# VFD_CLOCK.net
KiCad netlist of a schematic drawn in Altium Designer
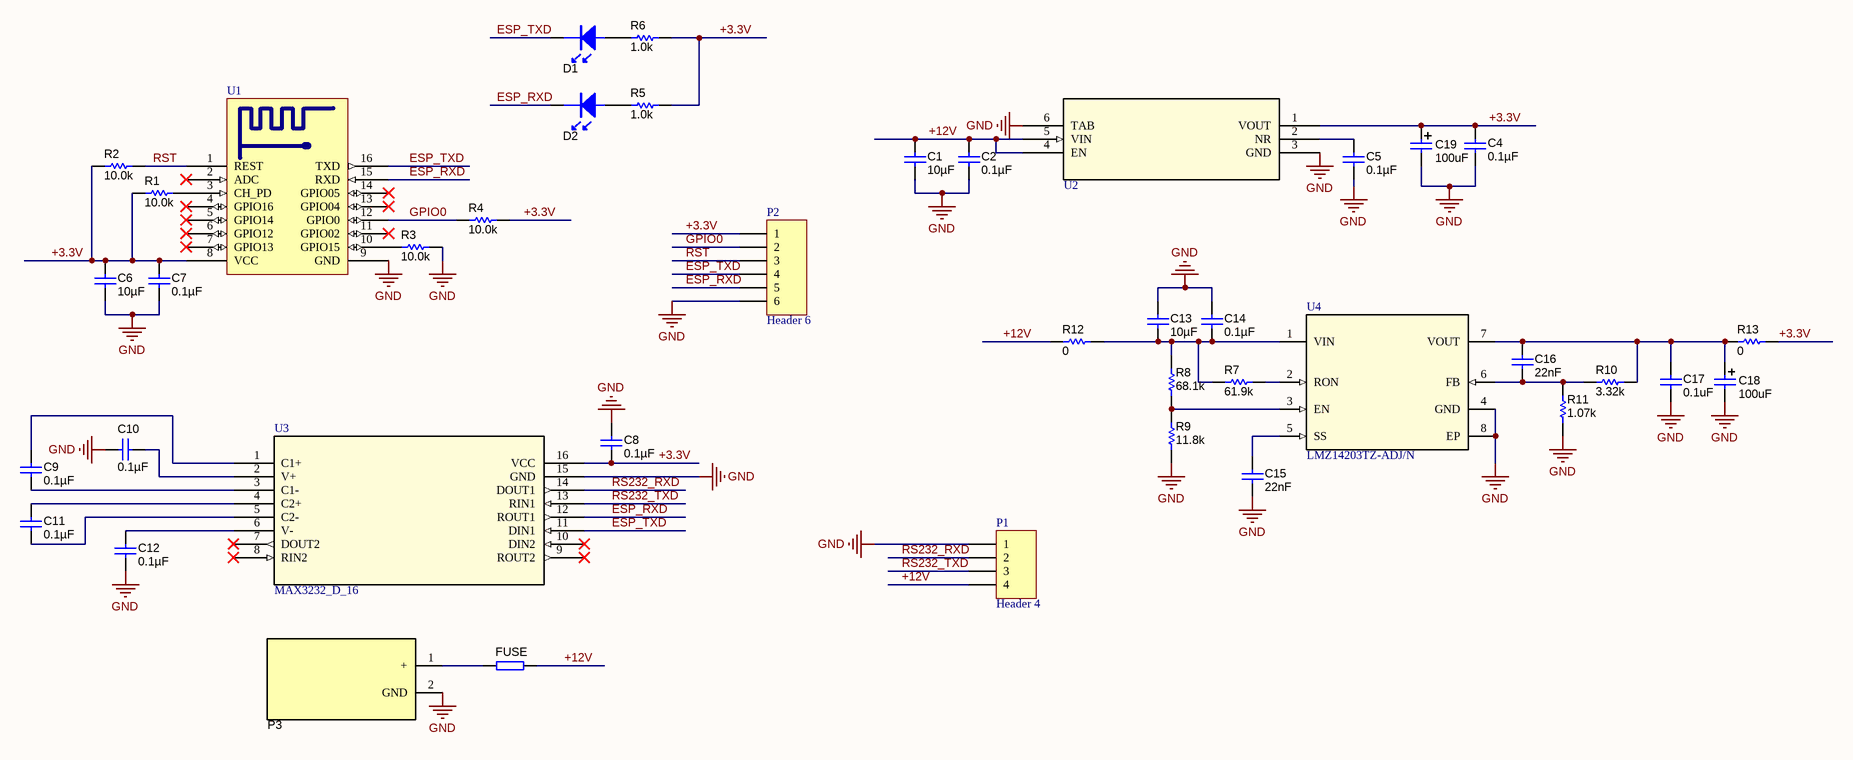
[diagram p0: VFD_CLOCK.SchDoc]

(export (version "E")
  (design (tool "Eeschema 10.0.6"))
  (components
    (comp (ref "C1")
      (value "0805YD106KAT2A")
      (footprint "0805_HV")
      (description "CAP, CERM, 10 µF, 16 V, +/- 10%, X5R, 0805")
      (fields
        (field (name "MANUFACTURER") "AVX")
        (field (name "VALUEDISPLAYED") "10µF")
        (field (name "PUBLISHER") "Texas Instruments")
      )
      (libsource (lib "VFD_CLOCK") (part "0805YD106KAT2A"))
    )
    (comp (ref "C2")
      (value "08051C103JAT2A")
      (footprint "0805_HV")
      (description "CAP, CERM, 0.01 µF, 100 V, +/- 5%, X7R, 0805")
      (fields
        (field (name "VALUEDISPLAYED") "0.1µF")
        (field (name "MANUFACTURER") "AVX")
        (field (name "PUBLISHER") "Texas Instruments")
      )
      (libsource (lib "VFD_CLOCK") (part "08051C103JAT2A"))
    )
    (comp (ref "C4")
      (value "08051C103JAT2A")
      (footprint "0805_HV")
      (description "CAP, CERM, 0.01 µF, 100 V, +/- 5%, X7R, 0805")
      (fields
        (field (name "VALUEDISPLAYED") "0.1µF")
        (field (name "MANUFACTURER") "AVX")
        (field (name "PUBLISHER") "Texas Instruments")
      )
      (libsource (lib "VFD_CLOCK") (part "08051C103JAT2A"))
    )
    (comp (ref "C5")
      (value "08051C103JAT2A")
      (footprint "0805_HV")
      (description "CAP, CERM, 0.01 µF, 100 V, +/- 5%, X7R, 0805")
      (fields
        (field (name "VALUEDISPLAYED") "0.1µF")
        (field (name "MANUFACTURER") "AVX")
        (field (name "PUBLISHER") "Texas Instruments")
      )
      (libsource (lib "VFD_CLOCK") (part "08051C103JAT2A"))
    )
    (comp (ref "C6")
      (value "0805YD106KAT2A")
      (footprint "0805_HV")
      (description "CAP, CERM, 10 µF, 16 V, +/- 10%, X5R, 0805")
      (fields
        (field (name "MANUFACTURER") "AVX")
        (field (name "VALUEDISPLAYED") "10µF")
        (field (name "PUBLISHER") "Texas Instruments")
      )
      (libsource (lib "VFD_CLOCK") (part "0805YD106KAT2A"))
    )
    (comp (ref "C7")
      (value "08051C103JAT2A")
      (footprint "0805_HV")
      (description "CAP, CERM, 0.01 µF, 100 V, +/- 5%, X7R, 0805")
      (fields
        (field (name "VALUEDISPLAYED") "0.1µF")
        (field (name "MANUFACTURER") "AVX")
        (field (name "PUBLISHER") "Texas Instruments")
      )
      (libsource (lib "VFD_CLOCK") (part "08051C103JAT2A"))
    )
    (comp (ref "C8")
      (value "08051C103JAT2A")
      (footprint "0805_HV")
      (description "CAP, CERM, 0.01 µF, 100 V, +/- 5%, X7R, 0805")
      (fields
        (field (name "VALUEDISPLAYED") "0.1µF")
        (field (name "MANUFACTURER") "AVX")
        (field (name "PUBLISHER") "Texas Instruments")
      )
      (libsource (lib "VFD_CLOCK") (part "08051C103JAT2A"))
    )
    (comp (ref "C9")
      (value "08051C103JAT2A")
      (footprint "0805_HV")
      (description "CAP, CERM, 0.01 µF, 100 V, +/- 5%, X7R, 0805")
      (fields
        (field (name "VALUEDISPLAYED") "0.1µF")
        (field (name "MANUFACTURER") "AVX")
        (field (name "PUBLISHER") "Texas Instruments")
      )
      (libsource (lib "VFD_CLOCK") (part "08051C103JAT2A"))
    )
    (comp (ref "C10")
      (value "08051C103JAT2A")
      (footprint "0805_HV")
      (description "CAP, CERM, 0.01 µF, 100 V, +/- 5%, X7R, 0805")
      (fields
        (field (name "VALUEDISPLAYED") "0.1µF")
        (field (name "MANUFACTURER") "AVX")
        (field (name "PUBLISHER") "Texas Instruments")
      )
      (libsource (lib "VFD_CLOCK") (part "08051C103JAT2A"))
    )
    (comp (ref "C11")
      (value "08051C103JAT2A")
      (footprint "0805_HV")
      (description "CAP, CERM, 0.01 µF, 100 V, +/- 5%, X7R, 0805")
      (fields
        (field (name "VALUEDISPLAYED") "0.1µF")
        (field (name "MANUFACTURER") "AVX")
        (field (name "PUBLISHER") "Texas Instruments")
      )
      (libsource (lib "VFD_CLOCK") (part "08051C103JAT2A"))
    )
    (comp (ref "C12")
      (value "08051C103JAT2A")
      (footprint "0805_HV")
      (description "CAP, CERM, 0.01 µF, 100 V, +/- 5%, X7R, 0805")
      (fields
        (field (name "VALUEDISPLAYED") "0.1µF")
        (field (name "MANUFACTURER") "AVX")
        (field (name "PUBLISHER") "Texas Instruments")
      )
      (libsource (lib "VFD_CLOCK") (part "08051C103JAT2A"))
    )
    (comp (ref "C13")
      (value "0805YD106KAT2A")
      (footprint "0805_HV")
      (description "CAP, CERM, 10 µF, 16 V, +/- 10%, X5R, 0805")
      (fields
        (field (name "MANUFACTURER") "AVX")
        (field (name "VALUEDISPLAYED") "10µF")
        (field (name "PUBLISHER") "Texas Instruments")
      )
      (libsource (lib "VFD_CLOCK") (part "0805YD106KAT2A"))
    )
    (comp (ref "C14")
      (value "08051C103JAT2A")
      (footprint "0805_HV")
      (description "CAP, CERM, 0.01 µF, 100 V, +/- 5%, X7R, 0805")
      (fields
        (field (name "VALUEDISPLAYED") "0.1µF")
        (field (name "MANUFACTURER") "AVX")
        (field (name "PUBLISHER") "Texas Instruments")
      )
      (libsource (lib "VFD_CLOCK") (part "08051C103JAT2A"))
    )
    (comp (ref "C15")
      (value "08051C103JAT2A")
      (footprint "0805_HV")
      (description "CAP, CERM, 0.01 µF, 100 V, +/- 5%, X7R, 0805")
      (fields
        (field (name "VALUEDISPLAYED") "22nF")
        (field (name "MANUFACTURER") "AVX")
        (field (name "PUBLISHER") "Texas Instruments")
      )
      (libsource (lib "VFD_CLOCK") (part "08051C103JAT2A"))
    )
    (comp (ref "C16")
      (value "08051C103JAT2A")
      (footprint "0805_HV")
      (description "CAP, CERM, 0.01 µF, 100 V, +/- 5%, X7R, 0805")
      (fields
        (field (name "VALUEDISPLAYED") "22nF")
        (field (name "MANUFACTURER") "AVX")
        (field (name "PUBLISHER") "Texas Instruments")
      )
      (libsource (lib "VFD_CLOCK") (part "08051C103JAT2A"))
    )
    (comp (ref "C17")
      (value "08051C103JAT2A")
      (footprint "0805_HV")
      (description "CAP, CERM, 0.01 µF, 100 V, +/- 5%, X7R, 0805")
      (fields
        (field (name "VALUEDISPLAYED") "0.1uF")
        (field (name "MANUFACTURER") "AVX")
        (field (name "PUBLISHER") "Texas Instruments")
      )
      (libsource (lib "VFD_CLOCK") (part "08051C103JAT2A"))
    )
    (comp (ref "C18")
      (value "100uF")
      (footprint "CAP")
      (fields (field (name "MANUFACTURER") "Used in BOM report"))
      (libsource (lib "Buffer_Board") (part "Cap_100uF"))
    )
    (comp (ref "C19")
      (value "100uF")
      (footprint "CAP")
      (fields (field (name "MANUFACTURER") "Used in BOM report"))
      (libsource (lib "Buffer_Board") (part "Cap_100uF"))
    )
    (comp (ref "D1")
      (value "RED")
      (footprint "LED0805")
      (description "LED发光管")
      (libsource (lib "Buffer_Board") (part "LED"))
    )
    (comp (ref "D2")
      (value "RED")
      (footprint "LED0805")
      (description "LED发光管")
      (libsource (lib "Buffer_Board") (part "LED"))
    )
    (comp (ref "FUSE")
      (value "~")
      (footprint "1206")
      (description "电阻")
      (libsource (lib "Buffer_Board") (part "R"))
    )
    (comp (ref "P1")
      (value "Header 4")
      (footprint "HDR1X4")
      (description "Header, 4-Pin")
      (fields (field (name "PUBLISHER") "Altium Limited"))
      (libsource (lib "Miscellaneous Connectors") (part "Header 4"))
    )
    (comp (ref "P2")
      (value "Header 6")
      (footprint "HDR1X6")
      (description "Header, 6-Pin")
      (fields (field (name "PUBLISHER") "Altium Limited"))
      (libsource (lib "VFD_CLOCK") (part "Header 6"))
    )
    (comp (ref "P3")
      (value "Used in BOM report")
      (footprint "PWR5.5")
      (libsource (lib "VFD_CLOCK") (part "PWR5.5"))
    )
    (comp (ref "R1")
      (value "CRCW080510K0FKEA")
      (footprint "0805_HV")
      (description "RES, 10.0 k, 1%, 0.125 W, 0805")
      (fields
        (field (name "MANUFACTURER") "Vishay-Dale")
        (field (name "VALUEDISPLAYED") "10.0k")
        (field (name "PUBLISHER") "Texas Instruments")
      )
      (libsource (lib "VFD_CLOCK") (part "CRCW080510K0FKEA"))
    )
    (comp (ref "R2")
      (value "CRCW080510K0FKEA")
      (footprint "0805_HV")
      (description "RES, 10.0 k, 1%, 0.125 W, 0805")
      (fields
        (field (name "MANUFACTURER") "Vishay-Dale")
        (field (name "VALUEDISPLAYED") "10.0k")
        (field (name "PUBLISHER") "Texas Instruments")
      )
      (libsource (lib "VFD_CLOCK") (part "CRCW080510K0FKEA"))
    )
    (comp (ref "R3")
      (value "CRCW080510K0FKEA")
      (footprint "0805_HV")
      (description "RES, 10.0 k, 1%, 0.125 W, 0805")
      (fields
        (field (name "MANUFACTURER") "Vishay-Dale")
        (field (name "VALUEDISPLAYED") "10.0k")
        (field (name "PUBLISHER") "Texas Instruments")
      )
      (libsource (lib "VFD_CLOCK") (part "CRCW080510K0FKEA"))
    )
    (comp (ref "R4")
      (value "CRCW080510K0FKEA")
      (footprint "0805_HV")
      (description "RES, 10.0 k, 1%, 0.125 W, 0805")
      (fields
        (field (name "MANUFACTURER") "Vishay-Dale")
        (field (name "VALUEDISPLAYED") "10.0k")
        (field (name "PUBLISHER") "Texas Instruments")
      )
      (libsource (lib "VFD_CLOCK") (part "CRCW080510K0FKEA"))
    )
    (comp (ref "R5")
      (value "CRCW080510K0FKEA")
      (footprint "0805_HV")
      (description "RES, 10.0 k, 1%, 0.125 W, 0805")
      (fields
        (field (name "MANUFACTURER") "Vishay-Dale")
        (field (name "VALUEDISPLAYED") "1.0k")
        (field (name "PUBLISHER") "Texas Instruments")
      )
      (libsource (lib "VFD_CLOCK") (part "CRCW080510K0FKEA"))
    )
    (comp (ref "R6")
      (value "CRCW080510K0FKEA")
      (footprint "0805_HV")
      (description "RES, 10.0 k, 1%, 0.125 W, 0805")
      (fields
        (field (name "MANUFACTURER") "Vishay-Dale")
        (field (name "VALUEDISPLAYED") "1.0k")
        (field (name "PUBLISHER") "Texas Instruments")
      )
      (libsource (lib "VFD_CLOCK") (part "CRCW080510K0FKEA"))
    )
    (comp (ref "R7")
      (value "CRCW080510K0FKEA")
      (footprint "0805_HV")
      (description "RES, 10.0 k, 1%, 0.125 W, 0805")
      (fields
        (field (name "MANUFACTURER") "Vishay-Dale")
        (field (name "VALUEDISPLAYED") "61.9k")
        (field (name "PUBLISHER") "Texas Instruments")
      )
      (libsource (lib "VFD_CLOCK") (part "CRCW080510K0FKEA"))
    )
    (comp (ref "R8")
      (value "CRCW080510K0FKEA")
      (footprint "0805_HV")
      (description "RES, 10.0 k, 1%, 0.125 W, 0805")
      (fields
        (field (name "MANUFACTURER") "Vishay-Dale")
        (field (name "VALUEDISPLAYED") "68.1k")
        (field (name "PUBLISHER") "Texas Instruments")
      )
      (libsource (lib "VFD_CLOCK") (part "CRCW080510K0FKEA"))
    )
    (comp (ref "R9")
      (value "CRCW080510K0FKEA")
      (footprint "0805_HV")
      (description "RES, 10.0 k, 1%, 0.125 W, 0805")
      (fields
        (field (name "MANUFACTURER") "Vishay-Dale")
        (field (name "VALUEDISPLAYED") "11.8k")
        (field (name "PUBLISHER") "Texas Instruments")
      )
      (libsource (lib "VFD_CLOCK") (part "CRCW080510K0FKEA"))
    )
    (comp (ref "R10")
      (value "CRCW080510K0FKEA")
      (footprint "0805_HV")
      (description "RES, 10.0 k, 1%, 0.125 W, 0805")
      (fields
        (field (name "MANUFACTURER") "Vishay-Dale")
        (field (name "VALUEDISPLAYED") "3.32k")
        (field (name "PUBLISHER") "Texas Instruments")
      )
      (libsource (lib "VFD_CLOCK") (part "CRCW080510K0FKEA"))
    )
    (comp (ref "R11")
      (value "CRCW080510K0FKEA")
      (footprint "0805_HV")
      (description "RES, 10.0 k, 1%, 0.125 W, 0805")
      (fields
        (field (name "MANUFACTURER") "Vishay-Dale")
        (field (name "VALUEDISPLAYED") "1.07k")
        (field (name "PUBLISHER") "Texas Instruments")
      )
      (libsource (lib "VFD_CLOCK") (part "CRCW080510K0FKEA"))
    )
    (comp (ref "R12")
      (value "CRCW080510K0FKEA")
      (footprint "0805_HV")
      (description "RES, 10.0 k, 1%, 0.125 W, 0805")
      (fields
        (field (name "MANUFACTURER") "Vishay-Dale")
        (field (name "VALUEDISPLAYED") "0")
        (field (name "PUBLISHER") "Texas Instruments")
      )
      (libsource (lib "VFD_CLOCK") (part "CRCW080510K0FKEA"))
    )
    (comp (ref "R13")
      (value "CRCW080510K0FKEA")
      (footprint "0805_HV")
      (description "RES, 10.0 k, 1%, 0.125 W, 0805")
      (fields
        (field (name "MANUFACTURER") "Vishay-Dale")
        (field (name "VALUEDISPLAYED") "0")
        (field (name "PUBLISHER") "Texas Instruments")
      )
      (libsource (lib "VFD_CLOCK") (part "CRCW080510K0FKEA"))
    )
    (comp (ref "U1") (value "ESP-12") (footprint "ESP_12") (libsource (lib "ESP-12") (part "ESP-12")))
    (comp (ref "U2")
      (value "REG104-33")
      (footprint "TO-263")
      (description "Imported")
      (fields (field (name "MANUFACTURER_PART_NUMBER") "lp38502ts-adjnopb"))
      (libsource (lib "2019-04-22_16-58-03") (part "REG104-33"))
    )
    (comp (ref "U3")
      (value "MAX3232_D_16")
      (footprint "D16")
      (description "Imported")
      (fields
        (field (name "MANUFACTURER") "Texas Instruments")
        (field (name "GENERIC_PART_NUMBER") "MAX3232")
      )
      (libsource (lib "2019-04-22_17-42-02") (part "MAX3232_D_16"))
    )
    (comp (ref "U4")
      (value "LMZ14203TZ-ADJ/N")
      (footprint "NDW0007A")
      (description "Imported")
      (fields
        (field (name "MANUFACTURER") "Texas Instruments")
        (field (name "PARTNUMBER") "LMZ14203TZ-ADJ/NOPB")
      )
      (libsource (lib "2019-04-23_14-14-10") (part "LMZ14203TZ-ADJ/N"))
    )
  )
  (nets
    (net (code "1") (name "/+3.3V") (class "Default")
      (node (ref "C19") (pin "1") (pinfunction "1_1") (pintype "passive"))
      (node (ref "C4") (pin "1") (pinfunction "1_1") (pintype "passive"))
      (node (ref "C6") (pin "1") (pinfunction "1_1") (pintype "passive"))
      (node (ref "C7") (pin "1") (pinfunction "1_1") (pintype "passive"))
      (node (ref "C8") (pin "1") (pinfunction "1_1") (pintype "passive"))
      (node (ref "P2") (pin "1") (pinfunction "1_1") (pintype "passive"))
      (node (ref "R1") (pin "2") (pinfunction "2_2") (pintype "passive"))
      (node (ref "R13") (pin "2") (pinfunction "2_2") (pintype "passive"))
      (node (ref "R2") (pin "2") (pinfunction "2_2") (pintype "passive"))
      (node (ref "R4") (pin "1") (pinfunction "1_1") (pintype "passive"))
      (node (ref "R5") (pin "1") (pinfunction "1_1") (pintype "passive"))
      (node (ref "R6") (pin "1") (pinfunction "1_1") (pintype "passive"))
      (node (ref "U1") (pin "8") (pinfunction "VCC_8") (pintype "power_in"))
      (node (ref "U2") (pin "1") (pinfunction "VOUT_1") (pintype "passive"))
      (node (ref "U3") (pin "16") (pinfunction "VCC_16") (pintype "power_in"))
    )
    (net (code "2") (name "/+12V") (class "Default")
      (node (ref "C1") (pin "1") (pinfunction "1_1") (pintype "passive"))
      (node (ref "C2") (pin "1") (pinfunction "1_1") (pintype "passive"))
      (node (ref "FUSE") (pin "2") (pinfunction "2_2") (pintype "passive"))
      (node (ref "P1") (pin "4") (pinfunction "4_4") (pintype "passive"))
      (node (ref "R12") (pin "1") (pinfunction "1_1") (pintype "passive"))
      (node (ref "U2") (pin "4") (pinfunction "EN_4") (pintype "power_in"))
      (node (ref "U2") (pin "5") (pinfunction "VIN_5") (pintype "input"))
    )
    (net (code "3") (name "/ESP_RXD") (class "Default")
      (node (ref "D2") (pin "2") (pinfunction "2_2") (pintype "passive"))
      (node (ref "P2") (pin "5") (pinfunction "5_5") (pintype "passive"))
      (node (ref "U1") (pin "15") (pinfunction "RXD_15") (pintype "input"))
      (node (ref "U3") (pin "12") (pinfunction "ROUT1_12") (pintype "output"))
    )
    (net (code "4") (name "/ESP_TXD") (class "Default")
      (node (ref "D1") (pin "2") (pinfunction "2_2") (pintype "passive"))
      (node (ref "P2") (pin "4") (pinfunction "4_4") (pintype "passive"))
      (node (ref "U1") (pin "16") (pinfunction "TXD_16") (pintype "output"))
      (node (ref "U3") (pin "11") (pinfunction "DIN1_11") (pintype "input"))
    )
    (net (code "5") (name "/GPIO0") (class "Default")
      (node (ref "P2") (pin "2") (pinfunction "2_2") (pintype "passive"))
      (node (ref "R4") (pin "2") (pinfunction "2_2") (pintype "passive"))
      (node (ref "U1") (pin "12") (pinfunction "GPIO0_12") (pintype "bidirectional"))
    )
    (net (code "6") (name "/RS232_RXD") (class "Default")
      (node (ref "P1") (pin "2") (pinfunction "2_2") (pintype "passive"))
      (node (ref "U3") (pin "14") (pinfunction "DOUT1_14") (pintype "output"))
    )
    (net (code "7") (name "/RS232_TXD") (class "Default")
      (node (ref "P1") (pin "3") (pinfunction "3_3") (pintype "passive"))
      (node (ref "U3") (pin "13") (pinfunction "RIN1_13") (pintype "input"))
    )
    (net (code "8") (name "/RST") (class "Default")
      (node (ref "P2") (pin "3") (pinfunction "3_3") (pintype "passive"))
      (node (ref "R2") (pin "1") (pinfunction "1_1") (pintype "passive"))
      (node (ref "U1") (pin "1") (pinfunction "REST_1") (pintype "passive"))
    )
    (net (code "9") (name "GND") (class "Default")
      (node (ref "C1") (pin "2") (pinfunction "2_2") (pintype "passive"))
      (node (ref "C10") (pin "2") (pinfunction "2_2") (pintype "passive"))
      (node (ref "C12") (pin "2") (pinfunction "2_2") (pintype "passive"))
      (node (ref "C13") (pin "1") (pinfunction "1_1") (pintype "passive"))
      (node (ref "C14") (pin "1") (pinfunction "1_1") (pintype "passive"))
      (node (ref "C15") (pin "1") (pinfunction "1_1") (pintype "passive"))
      (node (ref "C17") (pin "1") (pinfunction "1_1") (pintype "passive"))
      (node (ref "C18") (pin "2") (pinfunction "2_2") (pintype "passive"))
      (node (ref "C19") (pin "2") (pinfunction "2_2") (pintype "passive"))
      (node (ref "C2") (pin "2") (pinfunction "2_2") (pintype "passive"))
      (node (ref "C4") (pin "2") (pinfunction "2_2") (pintype "passive"))
      (node (ref "C5") (pin "2") (pinfunction "2_2") (pintype "passive"))
      (node (ref "C6") (pin "2") (pinfunction "2_2") (pintype "passive"))
      (node (ref "C7") (pin "2") (pinfunction "2_2") (pintype "passive"))
      (node (ref "C8") (pin "2") (pinfunction "2_2") (pintype "passive"))
      (node (ref "P1") (pin "1") (pinfunction "1_1") (pintype "passive"))
      (node (ref "P2") (pin "6") (pinfunction "6_6") (pintype "passive"))
      (node (ref "P3") (pin "2") (pinfunction "GND_2") (pintype "passive"))
      (node (ref "R11") (pin "2") (pinfunction "2_2") (pintype "passive"))
      (node (ref "R3") (pin "1") (pinfunction "1_1") (pintype "passive"))
      (node (ref "R9") (pin "2") (pinfunction "2_2") (pintype "passive"))
      (node (ref "U1") (pin "9") (pinfunction "GND_9") (pintype "power_in"))
      (node (ref "U2") (pin "3") (pinfunction "GND_3") (pintype "power_in"))
      (node (ref "U2") (pin "6") (pinfunction "TAB_6") (pintype "power_in"))
      (node (ref "U3") (pin "15") (pinfunction "GND_15") (pintype "power_in"))
      (node (ref "U4") (pin "4") (pinfunction "GND_4") (pintype "power_in"))
      (node (ref "U4") (pin "8") (pinfunction "EP_8") (pintype "power_in"))
    )
    (net (code "10") (name "Net-(D1-Pad1)") (class "Default")
      (node (ref "D1") (pin "1") (pinfunction "1_1") (pintype "passive"))
      (node (ref "R6") (pin "2") (pinfunction "2_2") (pintype "passive"))
    )
    (net (code "11") (name "Net-(D2-Pad1)") (class "Default")
      (node (ref "D2") (pin "1") (pinfunction "1_1") (pintype "passive"))
      (node (ref "R5") (pin "2") (pinfunction "2_2") (pintype "passive"))
    )
    (net (code "12") (name "Net-(P3-+)") (class "Default")
      (node (ref "FUSE") (pin "1") (pinfunction "1_1") (pintype "passive"))
      (node (ref "P3") (pin "1") (pinfunction "+_1") (pintype "passive"))
    )
    (net (code "13") (name "Net-(U1-CH_PD)") (class "Default")
      (node (ref "R1") (pin "1") (pinfunction "1_1") (pintype "passive"))
      (node (ref "U1") (pin "3") (pinfunction "CH_PD_3") (pintype "input"))
    )
    (net (code "14") (name "Net-(U1-GPIO15)") (class "Default")
      (node (ref "R3") (pin "2") (pinfunction "2_2") (pintype "passive"))
      (node (ref "U1") (pin "10") (pinfunction "GPIO15_10") (pintype "bidirectional"))
    )
    (net (code "15") (name "Net-(U2-NR)") (class "Default")
      (node (ref "C5") (pin "1") (pinfunction "1_1") (pintype "passive"))
      (node (ref "U2") (pin "2") (pinfunction "NR_2") (pintype "power_in"))
    )
    (net (code "16") (name "Net-(U3-C1+)") (class "Default")
      (node (ref "C9") (pin "2") (pinfunction "2_2") (pintype "passive"))
      (node (ref "U3") (pin "1") (pinfunction "C1+_1") (pintype "passive"))
    )
    (net (code "17") (name "Net-(U3-C1-)") (class "Default")
      (node (ref "C9") (pin "1") (pinfunction "1_1") (pintype "passive"))
      (node (ref "U3") (pin "3") (pinfunction "C1-_3") (pintype "passive"))
    )
    (net (code "18") (name "Net-(U3-C2+)") (class "Default")
      (node (ref "C11") (pin "2") (pinfunction "2_2") (pintype "passive"))
      (node (ref "U3") (pin "4") (pinfunction "C2+_4") (pintype "passive"))
    )
    (net (code "19") (name "Net-(U3-C2-)") (class "Default")
      (node (ref "C11") (pin "1") (pinfunction "1_1") (pintype "passive"))
      (node (ref "U3") (pin "5") (pinfunction "C2-_5") (pintype "passive"))
    )
    (net (code "20") (name "Net-(U3-V+)") (class "Default")
      (node (ref "C10") (pin "1") (pinfunction "1_1") (pintype "passive"))
      (node (ref "U3") (pin "2") (pinfunction "V+_2") (pintype "power_in"))
    )
    (net (code "21") (name "Net-(U3-V-)") (class "Default")
      (node (ref "C12") (pin "1") (pinfunction "1_1") (pintype "passive"))
      (node (ref "U3") (pin "6") (pinfunction "V-_6") (pintype "power_in"))
    )
    (net (code "22") (name "Net-(U4-EN)") (class "Default")
      (node (ref "R8") (pin "2") (pinfunction "2_2") (pintype "passive"))
      (node (ref "R9") (pin "1") (pinfunction "1_1") (pintype "passive"))
      (node (ref "U4") (pin "3") (pinfunction "EN_3") (pintype "input"))
    )
    (net (code "23") (name "Net-(U4-FB)") (class "Default")
      (node (ref "C16") (pin "1") (pinfunction "1_1") (pintype "passive"))
      (node (ref "R10") (pin "1") (pinfunction "1_1") (pintype "passive"))
      (node (ref "R11") (pin "1") (pinfunction "1_1") (pintype "passive"))
      (node (ref "U4") (pin "6") (pinfunction "FB_6") (pintype "input"))
    )
    (net (code "24") (name "Net-(U4-RON)") (class "Default")
      (node (ref "R7") (pin "1") (pinfunction "1_1") (pintype "passive"))
      (node (ref "U4") (pin "2") (pinfunction "RON_2") (pintype "input"))
    )
    (net (code "25") (name "Net-(U4-SS)") (class "Default")
      (node (ref "C15") (pin "2") (pinfunction "2_2") (pintype "passive"))
      (node (ref "U4") (pin "5") (pinfunction "SS_5") (pintype "input"))
    )
    (net (code "26") (name "Net-(U4-VIN)") (class "Default")
      (node (ref "C13") (pin "2") (pinfunction "2_2") (pintype "passive"))
      (node (ref "C14") (pin "2") (pinfunction "2_2") (pintype "passive"))
      (node (ref "R12") (pin "2") (pinfunction "2_2") (pintype "passive"))
      (node (ref "R7") (pin "2") (pinfunction "2_2") (pintype "passive"))
      (node (ref "R8") (pin "1") (pinfunction "1_1") (pintype "passive"))
      (node (ref "U4") (pin "1") (pinfunction "VIN_1") (pintype "power_in"))
    )
    (net (code "27") (name "Net-(U4-VOUT)") (class "Default")
      (node (ref "C16") (pin "2") (pinfunction "2_2") (pintype "passive"))
      (node (ref "C17") (pin "2") (pinfunction "2_2") (pintype "passive"))
      (node (ref "C18") (pin "1") (pinfunction "1_1") (pintype "passive"))
      (node (ref "R10") (pin "2") (pinfunction "2_2") (pintype "passive"))
      (node (ref "R13") (pin "1") (pinfunction "1_1") (pintype "passive"))
      (node (ref "U4") (pin "7") (pinfunction "VOUT_7") (pintype "power_in"))
    )
    (net (code "28") (name "unconnected-(U1-ADC-Pad2)") (class "Default")
      (node (ref "U1") (pin "2") (pinfunction "ADC_2") (pintype "input+no_connect"))
    )
    (net (code "29") (name "unconnected-(U1-GPIO02-Pad11)") (class "Default")
      (node (ref "U1") (pin "11") (pinfunction "GPIO02_11") (pintype "bidirectional+no_connect"))
    )
    (net (code "30") (name "unconnected-(U1-GPIO04-Pad13)") (class "Default")
      (node (ref "U1") (pin "13") (pinfunction "GPIO04_13") (pintype "bidirectional+no_connect"))
    )
    (net (code "31") (name "unconnected-(U1-GPIO05-Pad14)") (class "Default")
      (node (ref "U1") (pin "14") (pinfunction "GPIO05_14") (pintype "bidirectional+no_connect"))
    )
    (net (code "32") (name "unconnected-(U1-GPIO12-Pad6)") (class "Default")
      (node (ref "U1") (pin "6") (pinfunction "GPIO12_6") (pintype "bidirectional+no_connect"))
    )
    (net (code "33") (name "unconnected-(U1-GPIO13-Pad7)") (class "Default")
      (node (ref "U1") (pin "7") (pinfunction "GPIO13_7") (pintype "bidirectional+no_connect"))
    )
    (net (code "34") (name "unconnected-(U1-GPIO14-Pad5)") (class "Default")
      (node (ref "U1") (pin "5") (pinfunction "GPIO14_5") (pintype "bidirectional+no_connect"))
    )
    (net (code "35") (name "unconnected-(U1-GPIO16-Pad4)") (class "Default")
      (node (ref "U1") (pin "4") (pinfunction "GPIO16_4") (pintype "bidirectional+no_connect"))
    )
    (net (code "36") (name "unconnected-(U3-DIN2-Pad10)") (class "Default")
      (node (ref "U3") (pin "10") (pinfunction "DIN2_10") (pintype "input+no_connect"))
    )
    (net (code "37") (name "unconnected-(U3-DOUT2-Pad7)") (class "Default")
      (node (ref "U3") (pin "7") (pinfunction "DOUT2_7") (pintype "output+no_connect"))
    )
    (net (code "38") (name "unconnected-(U3-RIN2-Pad8)") (class "Default")
      (node (ref "U3") (pin "8") (pinfunction "RIN2_8") (pintype "input+no_connect"))
    )
    (net (code "39") (name "unconnected-(U3-ROUT2-Pad9)") (class "Default")
      (node (ref "U3") (pin "9") (pinfunction "ROUT2_9") (pintype "output+no_connect"))
    )
  )
)
